# SCH_8_MCP23017_IC_SS_2021-10-14.net
KiCad netlist of a schematic drawn in EasyEDA
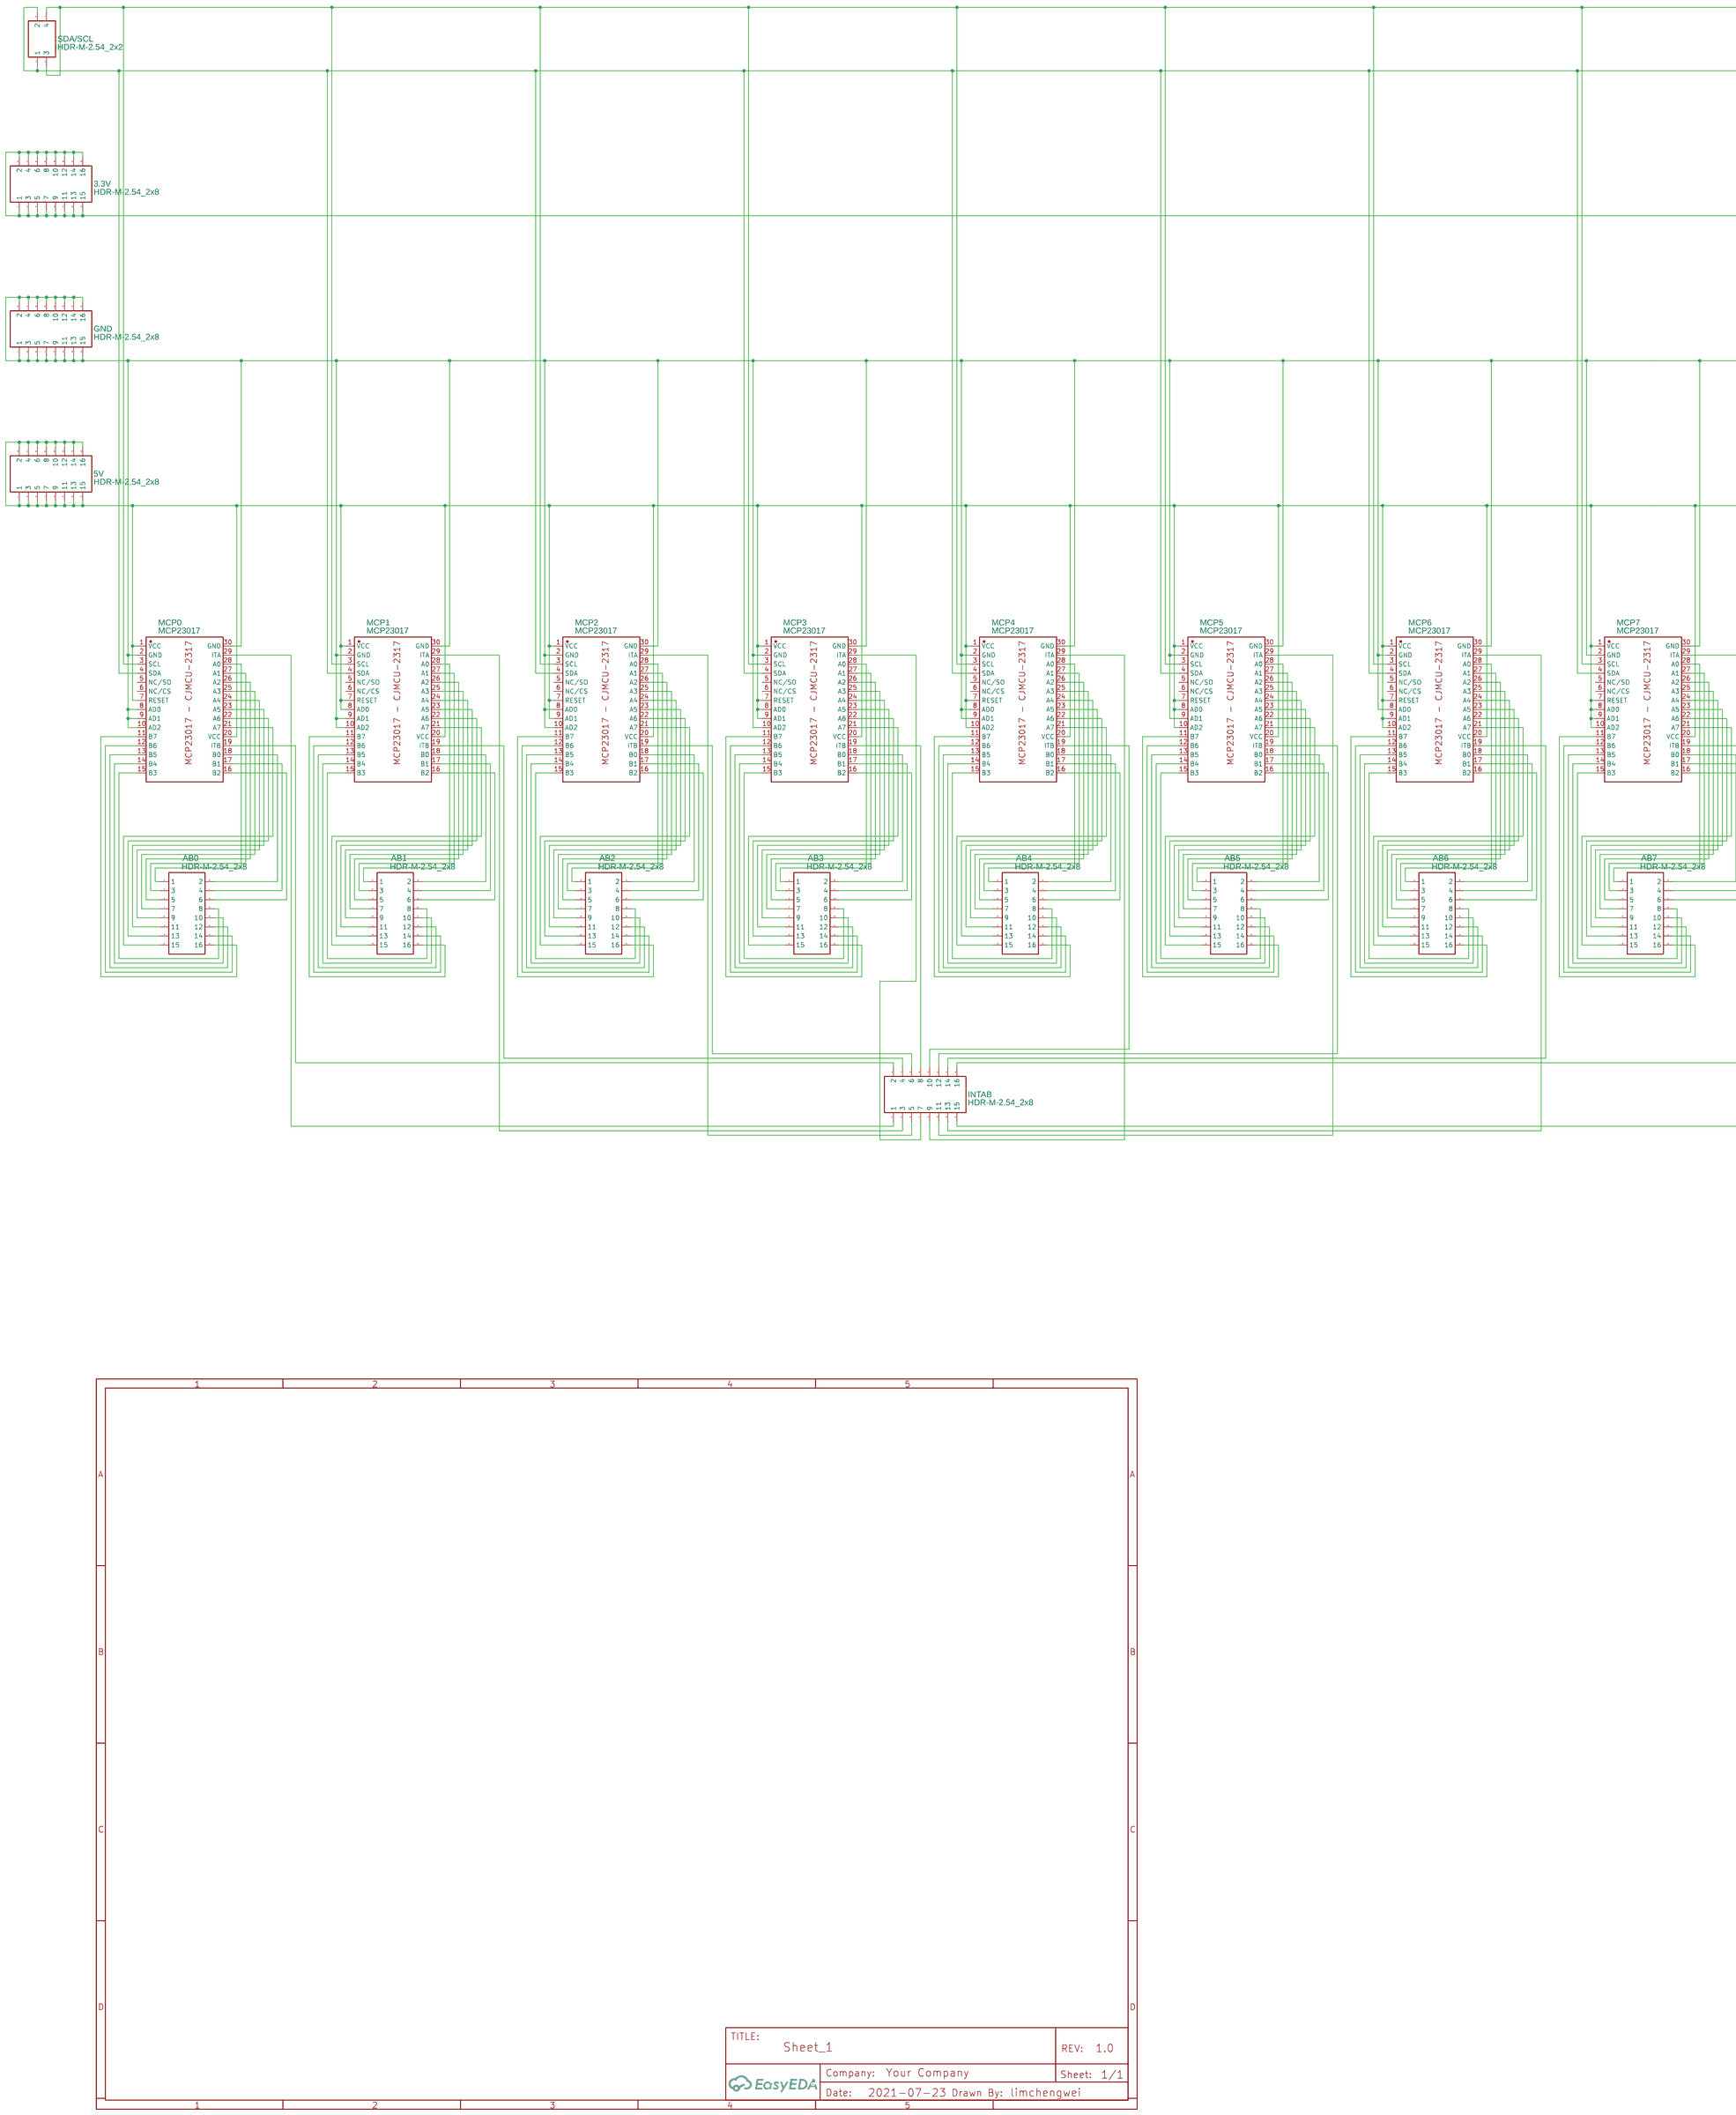
[diagram p0: schematic sheet]

(export (version "E")
  (design (tool "Eeschema 10.0.6"))
  (components
    (comp (ref "3.3V")
      (value "HDR-M-2.54_2x8")
      (fields (field (name "BOM_Supplier Part") "C68234"))
      (libsource (lib "") (part "HDR-M-2.54_2x8_3"))
    )
    (comp (ref "5V")
      (value "HDR-M-2.54_2x8")
      (fields (field (name "BOM_Supplier Part") "C68234"))
      (libsource (lib "") (part "HDR-M-2.54_2x8_1"))
    )
    (comp (ref "AB0")
      (value "HDR-M-2.54_2x8")
      (fields (field (name "BOM_Supplier Part") "C68234"))
      (libsource (lib "") (part "HDR-M-2.54_2x8"))
    )
    (comp (ref "AB1")
      (value "HDR-M-2.54_2x8")
      (fields (field (name "BOM_Supplier Part") "C68234"))
      (libsource (lib "") (part "HDR-M-2.54_2x8"))
    )
    (comp (ref "AB2")
      (value "HDR-M-2.54_2x8")
      (fields (field (name "BOM_Supplier Part") "C68234"))
      (libsource (lib "") (part "HDR-M-2.54_2x8"))
    )
    (comp (ref "AB3")
      (value "HDR-M-2.54_2x8")
      (fields (field (name "BOM_Supplier Part") "C68234"))
      (libsource (lib "") (part "HDR-M-2.54_2x8"))
    )
    (comp (ref "AB4")
      (value "HDR-M-2.54_2x8")
      (fields (field (name "BOM_Supplier Part") "C68234"))
      (libsource (lib "") (part "HDR-M-2.54_2x8"))
    )
    (comp (ref "AB5")
      (value "HDR-M-2.54_2x8")
      (fields (field (name "BOM_Supplier Part") "C68234"))
      (libsource (lib "") (part "HDR-M-2.54_2x8"))
    )
    (comp (ref "AB6")
      (value "HDR-M-2.54_2x8")
      (fields (field (name "BOM_Supplier Part") "C68234"))
      (libsource (lib "") (part "HDR-M-2.54_2x8"))
    )
    (comp (ref "AB7")
      (value "HDR-M-2.54_2x8")
      (fields (field (name "BOM_Supplier Part") "C68234"))
      (libsource (lib "") (part "HDR-M-2.54_2x8"))
    )
    (comp (ref "GND")
      (value "HDR-M-2.54_2x8")
      (fields (field (name "BOM_Supplier Part") "C68234"))
      (libsource (lib "") (part "HDR-M-2.54_2x8_4"))
    )
    (comp (ref "INTAB")
      (value "HDR-M-2.54_2x8")
      (fields (field (name "BOM_Supplier Part") "C68234"))
      (libsource (lib "") (part "HDR-M-2.54_2x8_2"))
    )
    (comp (ref "MCP0") (value "MCP23017") (libsource (lib "") (part "MCP23017")))
    (comp (ref "MCP1") (value "MCP23017") (libsource (lib "") (part "MCP23017")))
    (comp (ref "MCP2") (value "MCP23017") (libsource (lib "") (part "MCP23017")))
    (comp (ref "MCP3") (value "MCP23017") (libsource (lib "") (part "MCP23017")))
    (comp (ref "MCP4") (value "MCP23017") (libsource (lib "") (part "MCP23017")))
    (comp (ref "MCP5") (value "MCP23017") (libsource (lib "") (part "MCP23017")))
    (comp (ref "MCP6") (value "MCP23017") (libsource (lib "") (part "MCP23017")))
    (comp (ref "MCP7") (value "MCP23017") (libsource (lib "") (part "MCP23017")))
    (comp (ref "SDA/SCL")
      (value "HDR-M-2.54_2x2")
      (fields (field (name "BOM_Supplier Part") "C66690"))
      (libsource (lib "") (part "HDR-M-2.54_2x2"))
    )
  )
  (nets
    (net (code "1") (name "Net-(3.3V-Pad1)") (class "Default")
      (node (ref "3.3V") (pin "1") (pinfunction "1_1") (pintype "input"))
      (node (ref "3.3V") (pin "10") (pinfunction "10_10") (pintype "input"))
      (node (ref "3.3V") (pin "11") (pinfunction "11_11") (pintype "input"))
      (node (ref "3.3V") (pin "12") (pinfunction "12_12") (pintype "input"))
      (node (ref "3.3V") (pin "13") (pinfunction "13_13") (pintype "input"))
      (node (ref "3.3V") (pin "14") (pinfunction "14_14") (pintype "input"))
      (node (ref "3.3V") (pin "15") (pinfunction "15_15") (pintype "input"))
      (node (ref "3.3V") (pin "16") (pinfunction "16_16") (pintype "input"))
      (node (ref "3.3V") (pin "2") (pinfunction "2_2") (pintype "input"))
      (node (ref "3.3V") (pin "3") (pinfunction "3_3") (pintype "input"))
      (node (ref "3.3V") (pin "4") (pinfunction "4_4") (pintype "input"))
      (node (ref "3.3V") (pin "5") (pinfunction "5_5") (pintype "input"))
      (node (ref "3.3V") (pin "6") (pinfunction "6_6") (pintype "input"))
      (node (ref "3.3V") (pin "7") (pinfunction "7_7") (pintype "input"))
      (node (ref "3.3V") (pin "8") (pinfunction "8_8") (pintype "input"))
      (node (ref "3.3V") (pin "9") (pinfunction "9_9") (pintype "input"))
    )
    (net (code "2") (name "Net-(MCP0-A0)") (class "Default")
      (node (ref "AB0") (pin "1") (pinfunction "1_1") (pintype "input"))
      (node (ref "MCP0") (pin "28") (pinfunction "A0_28") (pintype "unspecified"))
    )
    (net (code "3") (name "Net-(MCP0-A1)") (class "Default")
      (node (ref "AB0") (pin "3") (pinfunction "3_3") (pintype "input"))
      (node (ref "MCP0") (pin "27") (pinfunction "A1_27") (pintype "unspecified"))
    )
    (net (code "4") (name "Net-(MCP0-A2)") (class "Default")
      (node (ref "AB0") (pin "5") (pinfunction "5_5") (pintype "input"))
      (node (ref "MCP0") (pin "26") (pinfunction "A2_26") (pintype "unspecified"))
    )
    (net (code "5") (name "Net-(MCP0-A3)") (class "Default")
      (node (ref "AB0") (pin "7") (pinfunction "7_7") (pintype "input"))
      (node (ref "MCP0") (pin "25") (pinfunction "A3_25") (pintype "unspecified"))
    )
    (net (code "6") (name "Net-(MCP0-A4)") (class "Default")
      (node (ref "AB0") (pin "9") (pinfunction "9_9") (pintype "input"))
      (node (ref "MCP0") (pin "24") (pinfunction "A4_24") (pintype "unspecified"))
    )
    (net (code "7") (name "Net-(MCP0-A5)") (class "Default")
      (node (ref "AB0") (pin "11") (pinfunction "11_11") (pintype "input"))
      (node (ref "MCP0") (pin "23") (pinfunction "A5_23") (pintype "unspecified"))
    )
    (net (code "8") (name "Net-(MCP0-A6)") (class "Default")
      (node (ref "AB0") (pin "13") (pinfunction "13_13") (pintype "input"))
      (node (ref "MCP0") (pin "22") (pinfunction "A6_22") (pintype "unspecified"))
    )
    (net (code "9") (name "Net-(MCP0-A7)") (class "Default")
      (node (ref "AB0") (pin "15") (pinfunction "15_15") (pintype "input"))
      (node (ref "MCP0") (pin "21") (pinfunction "A7_21") (pintype "unspecified"))
    )
    (net (code "10") (name "Net-(MCP0-AD0)") (class "Default")
      (node (ref "GND") (pin "1") (pinfunction "1_1") (pintype "input"))
      (node (ref "GND") (pin "10") (pinfunction "10_10") (pintype "input"))
      (node (ref "GND") (pin "11") (pinfunction "11_11") (pintype "input"))
      (node (ref "GND") (pin "12") (pinfunction "12_12") (pintype "input"))
      (node (ref "GND") (pin "13") (pinfunction "13_13") (pintype "input"))
      (node (ref "GND") (pin "14") (pinfunction "14_14") (pintype "input"))
      (node (ref "GND") (pin "15") (pinfunction "15_15") (pintype "input"))
      (node (ref "GND") (pin "16") (pinfunction "16_16") (pintype "input"))
      (node (ref "GND") (pin "2") (pinfunction "2_2") (pintype "input"))
      (node (ref "GND") (pin "3") (pinfunction "3_3") (pintype "input"))
      (node (ref "GND") (pin "4") (pinfunction "4_4") (pintype "input"))
      (node (ref "GND") (pin "5") (pinfunction "5_5") (pintype "input"))
      (node (ref "GND") (pin "6") (pinfunction "6_6") (pintype "input"))
      (node (ref "GND") (pin "7") (pinfunction "7_7") (pintype "input"))
      (node (ref "GND") (pin "8") (pinfunction "8_8") (pintype "input"))
      (node (ref "GND") (pin "9") (pinfunction "9_9") (pintype "input"))
      (node (ref "MCP0") (pin "10") (pinfunction "AD2_10") (pintype "unspecified"))
      (node (ref "MCP0") (pin "2") (pinfunction "GND_2") (pintype "passive"))
      (node (ref "MCP0") (pin "30") (pinfunction "GND_30") (pintype "passive"))
      (node (ref "MCP0") (pin "8") (pinfunction "AD0_8") (pintype "unspecified"))
      (node (ref "MCP0") (pin "9") (pinfunction "AD1_9") (pintype "unspecified"))
      (node (ref "MCP1") (pin "10") (pinfunction "AD2_10") (pintype "unspecified"))
      (node (ref "MCP1") (pin "2") (pinfunction "GND_2") (pintype "passive"))
      (node (ref "MCP1") (pin "30") (pinfunction "GND_30") (pintype "passive"))
      (node (ref "MCP1") (pin "9") (pinfunction "AD1_9") (pintype "unspecified"))
      (node (ref "MCP2") (pin "10") (pinfunction "AD2_10") (pintype "unspecified"))
      (node (ref "MCP2") (pin "2") (pinfunction "GND_2") (pintype "passive"))
      (node (ref "MCP2") (pin "30") (pinfunction "GND_30") (pintype "passive"))
      (node (ref "MCP2") (pin "8") (pinfunction "AD0_8") (pintype "unspecified"))
      (node (ref "MCP3") (pin "10") (pinfunction "AD2_10") (pintype "unspecified"))
      (node (ref "MCP3") (pin "2") (pinfunction "GND_2") (pintype "passive"))
      (node (ref "MCP3") (pin "30") (pinfunction "GND_30") (pintype "passive"))
      (node (ref "MCP4") (pin "2") (pinfunction "GND_2") (pintype "passive"))
      (node (ref "MCP4") (pin "30") (pinfunction "GND_30") (pintype "passive"))
      (node (ref "MCP4") (pin "8") (pinfunction "AD0_8") (pintype "unspecified"))
      (node (ref "MCP4") (pin "9") (pinfunction "AD1_9") (pintype "unspecified"))
      (node (ref "MCP5") (pin "2") (pinfunction "GND_2") (pintype "passive"))
      (node (ref "MCP5") (pin "30") (pinfunction "GND_30") (pintype "passive"))
      (node (ref "MCP5") (pin "9") (pinfunction "AD1_9") (pintype "unspecified"))
      (node (ref "MCP6") (pin "2") (pinfunction "GND_2") (pintype "passive"))
      (node (ref "MCP6") (pin "30") (pinfunction "GND_30") (pintype "passive"))
      (node (ref "MCP6") (pin "8") (pinfunction "AD0_8") (pintype "unspecified"))
      (node (ref "MCP7") (pin "2") (pinfunction "GND_2") (pintype "passive"))
      (node (ref "MCP7") (pin "30") (pinfunction "GND_30") (pintype "passive"))
    )
    (net (code "11") (name "Net-(MCP0-B0)") (class "Default")
      (node (ref "AB0") (pin "2") (pinfunction "2_2") (pintype "input"))
      (node (ref "MCP0") (pin "18") (pinfunction "B0_18") (pintype "unspecified"))
    )
    (net (code "12") (name "Net-(MCP0-B1)") (class "Default")
      (node (ref "AB0") (pin "4") (pinfunction "4_4") (pintype "input"))
      (node (ref "MCP0") (pin "17") (pinfunction "B1_17") (pintype "unspecified"))
    )
    (net (code "13") (name "Net-(MCP0-B2)") (class "Default")
      (node (ref "AB0") (pin "6") (pinfunction "6_6") (pintype "input"))
      (node (ref "MCP0") (pin "16") (pinfunction "B2_16") (pintype "unspecified"))
    )
    (net (code "14") (name "Net-(MCP0-B3)") (class "Default")
      (node (ref "AB0") (pin "8") (pinfunction "8_8") (pintype "input"))
      (node (ref "MCP0") (pin "15") (pinfunction "B3_15") (pintype "unspecified"))
    )
    (net (code "15") (name "Net-(MCP0-B4)") (class "Default")
      (node (ref "AB0") (pin "10") (pinfunction "10_10") (pintype "input"))
      (node (ref "MCP0") (pin "14") (pinfunction "B4_14") (pintype "unspecified"))
    )
    (net (code "16") (name "Net-(MCP0-B5)") (class "Default")
      (node (ref "AB0") (pin "12") (pinfunction "12_12") (pintype "input"))
      (node (ref "MCP0") (pin "13") (pinfunction "B5_13") (pintype "unspecified"))
    )
    (net (code "17") (name "Net-(MCP0-B6)") (class "Default")
      (node (ref "AB0") (pin "14") (pinfunction "14_14") (pintype "input"))
      (node (ref "MCP0") (pin "12") (pinfunction "B6_12") (pintype "unspecified"))
    )
    (net (code "18") (name "Net-(MCP0-B7)") (class "Default")
      (node (ref "AB0") (pin "16") (pinfunction "16_16") (pintype "input"))
      (node (ref "MCP0") (pin "11") (pinfunction "B7_11") (pintype "unspecified"))
    )
    (net (code "19") (name "Net-(MCP0-ITA)") (class "Default")
      (node (ref "INTAB") (pin "1") (pinfunction "1_1") (pintype "input"))
      (node (ref "MCP0") (pin "29") (pinfunction "ITA_29") (pintype "unspecified"))
    )
    (net (code "20") (name "Net-(MCP0-ITB)") (class "Default")
      (node (ref "INTAB") (pin "2") (pinfunction "2_2") (pintype "input"))
      (node (ref "MCP0") (pin "19") (pinfunction "ITB_19") (pintype "unspecified"))
    )
    (net (code "21") (name "Net-(MCP0-RESET)") (class "Default")
      (node (ref "5V") (pin "1") (pinfunction "1_1") (pintype "input"))
      (node (ref "5V") (pin "10") (pinfunction "10_10") (pintype "input"))
      (node (ref "5V") (pin "11") (pinfunction "11_11") (pintype "input"))
      (node (ref "5V") (pin "12") (pinfunction "12_12") (pintype "input"))
      (node (ref "5V") (pin "13") (pinfunction "13_13") (pintype "input"))
      (node (ref "5V") (pin "14") (pinfunction "14_14") (pintype "input"))
      (node (ref "5V") (pin "15") (pinfunction "15_15") (pintype "input"))
      (node (ref "5V") (pin "16") (pinfunction "16_16") (pintype "input"))
      (node (ref "5V") (pin "2") (pinfunction "2_2") (pintype "input"))
      (node (ref "5V") (pin "3") (pinfunction "3_3") (pintype "input"))
      (node (ref "5V") (pin "4") (pinfunction "4_4") (pintype "input"))
      (node (ref "5V") (pin "5") (pinfunction "5_5") (pintype "input"))
      (node (ref "5V") (pin "6") (pinfunction "6_6") (pintype "input"))
      (node (ref "5V") (pin "7") (pinfunction "7_7") (pintype "input"))
      (node (ref "5V") (pin "8") (pinfunction "8_8") (pintype "input"))
      (node (ref "5V") (pin "9") (pinfunction "9_9") (pintype "input"))
      (node (ref "MCP0") (pin "1") (pinfunction "VCC_1") (pintype "passive"))
      (node (ref "MCP0") (pin "20") (pinfunction "VCC_20") (pintype "passive"))
      (node (ref "MCP0") (pin "7") (pinfunction "RESET_7") (pintype "input"))
      (node (ref "MCP1") (pin "1") (pinfunction "VCC_1") (pintype "passive"))
      (node (ref "MCP1") (pin "20") (pinfunction "VCC_20") (pintype "passive"))
      (node (ref "MCP1") (pin "7") (pinfunction "RESET_7") (pintype "input"))
      (node (ref "MCP1") (pin "8") (pinfunction "AD0_8") (pintype "unspecified"))
      (node (ref "MCP2") (pin "1") (pinfunction "VCC_1") (pintype "passive"))
      (node (ref "MCP2") (pin "20") (pinfunction "VCC_20") (pintype "passive"))
      (node (ref "MCP2") (pin "7") (pinfunction "RESET_7") (pintype "input"))
      (node (ref "MCP2") (pin "9") (pinfunction "AD1_9") (pintype "unspecified"))
      (node (ref "MCP3") (pin "1") (pinfunction "VCC_1") (pintype "passive"))
      (node (ref "MCP3") (pin "20") (pinfunction "VCC_20") (pintype "passive"))
      (node (ref "MCP3") (pin "7") (pinfunction "RESET_7") (pintype "input"))
      (node (ref "MCP3") (pin "8") (pinfunction "AD0_8") (pintype "unspecified"))
      (node (ref "MCP3") (pin "9") (pinfunction "AD1_9") (pintype "unspecified"))
      (node (ref "MCP4") (pin "1") (pinfunction "VCC_1") (pintype "passive"))
      (node (ref "MCP4") (pin "10") (pinfunction "AD2_10") (pintype "unspecified"))
      (node (ref "MCP4") (pin "20") (pinfunction "VCC_20") (pintype "passive"))
      (node (ref "MCP4") (pin "7") (pinfunction "RESET_7") (pintype "input"))
      (node (ref "MCP5") (pin "1") (pinfunction "VCC_1") (pintype "passive"))
      (node (ref "MCP5") (pin "10") (pinfunction "AD2_10") (pintype "unspecified"))
      (node (ref "MCP5") (pin "20") (pinfunction "VCC_20") (pintype "passive"))
      (node (ref "MCP5") (pin "7") (pinfunction "RESET_7") (pintype "input"))
      (node (ref "MCP5") (pin "8") (pinfunction "AD0_8") (pintype "unspecified"))
      (node (ref "MCP6") (pin "1") (pinfunction "VCC_1") (pintype "passive"))
      (node (ref "MCP6") (pin "10") (pinfunction "AD2_10") (pintype "unspecified"))
      (node (ref "MCP6") (pin "20") (pinfunction "VCC_20") (pintype "passive"))
      (node (ref "MCP6") (pin "7") (pinfunction "RESET_7") (pintype "input"))
      (node (ref "MCP6") (pin "9") (pinfunction "AD1_9") (pintype "unspecified"))
      (node (ref "MCP7") (pin "1") (pinfunction "VCC_1") (pintype "passive"))
      (node (ref "MCP7") (pin "10") (pinfunction "AD2_10") (pintype "unspecified"))
      (node (ref "MCP7") (pin "20") (pinfunction "VCC_20") (pintype "passive"))
      (node (ref "MCP7") (pin "7") (pinfunction "RESET_7") (pintype "input"))
      (node (ref "MCP7") (pin "8") (pinfunction "AD0_8") (pintype "unspecified"))
      (node (ref "MCP7") (pin "9") (pinfunction "AD1_9") (pintype "unspecified"))
    )
    (net (code "22") (name "Net-(MCP0-SCL)") (class "Default")
      (node (ref "MCP0") (pin "3") (pinfunction "SCL_3") (pintype "bidirectional"))
      (node (ref "MCP1") (pin "3") (pinfunction "SCL_3") (pintype "bidirectional"))
      (node (ref "MCP2") (pin "3") (pinfunction "SCL_3") (pintype "bidirectional"))
      (node (ref "MCP3") (pin "3") (pinfunction "SCL_3") (pintype "bidirectional"))
      (node (ref "MCP4") (pin "3") (pinfunction "SCL_3") (pintype "bidirectional"))
      (node (ref "MCP5") (pin "3") (pinfunction "SCL_3") (pintype "bidirectional"))
      (node (ref "MCP6") (pin "3") (pinfunction "SCL_3") (pintype "bidirectional"))
      (node (ref "MCP7") (pin "3") (pinfunction "SCL_3") (pintype "bidirectional"))
      (node (ref "SDA/SCL") (pin "3") (pinfunction "3_3") (pintype "input"))
      (node (ref "SDA/SCL") (pin "4") (pinfunction "4_4") (pintype "input"))
    )
    (net (code "23") (name "Net-(MCP0-SDA)") (class "Default")
      (node (ref "MCP0") (pin "4") (pinfunction "SDA_4") (pintype "bidirectional"))
      (node (ref "MCP1") (pin "4") (pinfunction "SDA_4") (pintype "bidirectional"))
      (node (ref "MCP2") (pin "4") (pinfunction "SDA_4") (pintype "bidirectional"))
      (node (ref "MCP3") (pin "4") (pinfunction "SDA_4") (pintype "bidirectional"))
      (node (ref "MCP4") (pin "4") (pinfunction "SDA_4") (pintype "bidirectional"))
      (node (ref "MCP5") (pin "4") (pinfunction "SDA_4") (pintype "bidirectional"))
      (node (ref "MCP6") (pin "4") (pinfunction "SDA_4") (pintype "bidirectional"))
      (node (ref "MCP7") (pin "4") (pinfunction "SDA_4") (pintype "bidirectional"))
      (node (ref "SDA/SCL") (pin "1") (pinfunction "1_1") (pintype "input"))
      (node (ref "SDA/SCL") (pin "2") (pinfunction "2_2") (pintype "input"))
    )
    (net (code "24") (name "Net-(MCP1-A0)") (class "Default")
      (node (ref "AB1") (pin "1") (pinfunction "1_1") (pintype "input"))
      (node (ref "MCP1") (pin "28") (pinfunction "A0_28") (pintype "unspecified"))
    )
    (net (code "25") (name "Net-(MCP1-A1)") (class "Default")
      (node (ref "AB1") (pin "3") (pinfunction "3_3") (pintype "input"))
      (node (ref "MCP1") (pin "27") (pinfunction "A1_27") (pintype "unspecified"))
    )
    (net (code "26") (name "Net-(MCP1-A2)") (class "Default")
      (node (ref "AB1") (pin "5") (pinfunction "5_5") (pintype "input"))
      (node (ref "MCP1") (pin "26") (pinfunction "A2_26") (pintype "unspecified"))
    )
    (net (code "27") (name "Net-(MCP1-A3)") (class "Default")
      (node (ref "AB1") (pin "7") (pinfunction "7_7") (pintype "input"))
      (node (ref "MCP1") (pin "25") (pinfunction "A3_25") (pintype "unspecified"))
    )
    (net (code "28") (name "Net-(MCP1-A4)") (class "Default")
      (node (ref "AB1") (pin "9") (pinfunction "9_9") (pintype "input"))
      (node (ref "MCP1") (pin "24") (pinfunction "A4_24") (pintype "unspecified"))
    )
    (net (code "29") (name "Net-(MCP1-A5)") (class "Default")
      (node (ref "AB1") (pin "11") (pinfunction "11_11") (pintype "input"))
      (node (ref "MCP1") (pin "23") (pinfunction "A5_23") (pintype "unspecified"))
    )
    (net (code "30") (name "Net-(MCP1-A6)") (class "Default")
      (node (ref "AB1") (pin "13") (pinfunction "13_13") (pintype "input"))
      (node (ref "MCP1") (pin "22") (pinfunction "A6_22") (pintype "unspecified"))
    )
    (net (code "31") (name "Net-(MCP1-A7)") (class "Default")
      (node (ref "AB1") (pin "15") (pinfunction "15_15") (pintype "input"))
      (node (ref "MCP1") (pin "21") (pinfunction "A7_21") (pintype "unspecified"))
    )
    (net (code "32") (name "Net-(MCP1-B0)") (class "Default")
      (node (ref "AB1") (pin "2") (pinfunction "2_2") (pintype "input"))
      (node (ref "MCP1") (pin "18") (pinfunction "B0_18") (pintype "unspecified"))
    )
    (net (code "33") (name "Net-(MCP1-B1)") (class "Default")
      (node (ref "AB1") (pin "4") (pinfunction "4_4") (pintype "input"))
      (node (ref "MCP1") (pin "17") (pinfunction "B1_17") (pintype "unspecified"))
    )
    (net (code "34") (name "Net-(MCP1-B2)") (class "Default")
      (node (ref "AB1") (pin "6") (pinfunction "6_6") (pintype "input"))
      (node (ref "MCP1") (pin "16") (pinfunction "B2_16") (pintype "unspecified"))
    )
    (net (code "35") (name "Net-(MCP1-B3)") (class "Default")
      (node (ref "AB1") (pin "8") (pinfunction "8_8") (pintype "input"))
      (node (ref "MCP1") (pin "15") (pinfunction "B3_15") (pintype "unspecified"))
    )
    (net (code "36") (name "Net-(MCP1-B4)") (class "Default")
      (node (ref "AB1") (pin "10") (pinfunction "10_10") (pintype "input"))
      (node (ref "MCP1") (pin "14") (pinfunction "B4_14") (pintype "unspecified"))
    )
    (net (code "37") (name "Net-(MCP1-B5)") (class "Default")
      (node (ref "AB1") (pin "12") (pinfunction "12_12") (pintype "input"))
      (node (ref "MCP1") (pin "13") (pinfunction "B5_13") (pintype "unspecified"))
    )
    (net (code "38") (name "Net-(MCP1-B6)") (class "Default")
      (node (ref "AB1") (pin "14") (pinfunction "14_14") (pintype "input"))
      (node (ref "MCP1") (pin "12") (pinfunction "B6_12") (pintype "unspecified"))
    )
    (net (code "39") (name "Net-(MCP1-B7)") (class "Default")
      (node (ref "AB1") (pin "16") (pinfunction "16_16") (pintype "input"))
      (node (ref "MCP1") (pin "11") (pinfunction "B7_11") (pintype "unspecified"))
    )
    (net (code "40") (name "Net-(MCP1-ITA)") (class "Default")
      (node (ref "INTAB") (pin "3") (pinfunction "3_3") (pintype "input"))
      (node (ref "MCP1") (pin "29") (pinfunction "ITA_29") (pintype "unspecified"))
    )
    (net (code "41") (name "Net-(MCP1-ITB)") (class "Default")
      (node (ref "INTAB") (pin "4") (pinfunction "4_4") (pintype "input"))
      (node (ref "MCP1") (pin "19") (pinfunction "ITB_19") (pintype "unspecified"))
    )
    (net (code "42") (name "Net-(MCP2-A0)") (class "Default")
      (node (ref "AB2") (pin "1") (pinfunction "1_1") (pintype "input"))
      (node (ref "MCP2") (pin "28") (pinfunction "A0_28") (pintype "unspecified"))
    )
    (net (code "43") (name "Net-(MCP2-A1)") (class "Default")
      (node (ref "AB2") (pin "3") (pinfunction "3_3") (pintype "input"))
      (node (ref "MCP2") (pin "27") (pinfunction "A1_27") (pintype "unspecified"))
    )
    (net (code "44") (name "Net-(MCP2-A2)") (class "Default")
      (node (ref "AB2") (pin "5") (pinfunction "5_5") (pintype "input"))
      (node (ref "MCP2") (pin "26") (pinfunction "A2_26") (pintype "unspecified"))
    )
    (net (code "45") (name "Net-(MCP2-A3)") (class "Default")
      (node (ref "AB2") (pin "7") (pinfunction "7_7") (pintype "input"))
      (node (ref "MCP2") (pin "25") (pinfunction "A3_25") (pintype "unspecified"))
    )
    (net (code "46") (name "Net-(MCP2-A4)") (class "Default")
      (node (ref "AB2") (pin "9") (pinfunction "9_9") (pintype "input"))
      (node (ref "MCP2") (pin "24") (pinfunction "A4_24") (pintype "unspecified"))
    )
    (net (code "47") (name "Net-(MCP2-A5)") (class "Default")
      (node (ref "AB2") (pin "11") (pinfunction "11_11") (pintype "input"))
      (node (ref "MCP2") (pin "23") (pinfunction "A5_23") (pintype "unspecified"))
    )
    (net (code "48") (name "Net-(MCP2-A6)") (class "Default")
      (node (ref "AB2") (pin "13") (pinfunction "13_13") (pintype "input"))
      (node (ref "MCP2") (pin "22") (pinfunction "A6_22") (pintype "unspecified"))
    )
    (net (code "49") (name "Net-(MCP2-A7)") (class "Default")
      (node (ref "AB2") (pin "15") (pinfunction "15_15") (pintype "input"))
      (node (ref "MCP2") (pin "21") (pinfunction "A7_21") (pintype "unspecified"))
    )
    (net (code "50") (name "Net-(MCP2-B0)") (class "Default")
      (node (ref "AB2") (pin "2") (pinfunction "2_2") (pintype "input"))
      (node (ref "MCP2") (pin "18") (pinfunction "B0_18") (pintype "unspecified"))
    )
    (net (code "51") (name "Net-(MCP2-B1)") (class "Default")
      (node (ref "AB2") (pin "4") (pinfunction "4_4") (pintype "input"))
      (node (ref "MCP2") (pin "17") (pinfunction "B1_17") (pintype "unspecified"))
    )
    (net (code "52") (name "Net-(MCP2-B2)") (class "Default")
      (node (ref "AB2") (pin "6") (pinfunction "6_6") (pintype "input"))
      (node (ref "MCP2") (pin "16") (pinfunction "B2_16") (pintype "unspecified"))
    )
    (net (code "53") (name "Net-(MCP2-B3)") (class "Default")
      (node (ref "AB2") (pin "8") (pinfunction "8_8") (pintype "input"))
      (node (ref "MCP2") (pin "15") (pinfunction "B3_15") (pintype "unspecified"))
    )
    (net (code "54") (name "Net-(MCP2-B4)") (class "Default")
      (node (ref "AB2") (pin "10") (pinfunction "10_10") (pintype "input"))
      (node (ref "MCP2") (pin "14") (pinfunction "B4_14") (pintype "unspecified"))
    )
    (net (code "55") (name "Net-(MCP2-B5)") (class "Default")
      (node (ref "AB2") (pin "12") (pinfunction "12_12") (pintype "input"))
      (node (ref "MCP2") (pin "13") (pinfunction "B5_13") (pintype "unspecified"))
    )
    (net (code "56") (name "Net-(MCP2-B6)") (class "Default")
      (node (ref "AB2") (pin "14") (pinfunction "14_14") (pintype "input"))
      (node (ref "MCP2") (pin "12") (pinfunction "B6_12") (pintype "unspecified"))
    )
    (net (code "57") (name "Net-(MCP2-B7)") (class "Default")
      (node (ref "AB2") (pin "16") (pinfunction "16_16") (pintype "input"))
      (node (ref "MCP2") (pin "11") (pinfunction "B7_11") (pintype "unspecified"))
    )
    (net (code "58") (name "Net-(MCP2-ITA)") (class "Default")
      (node (ref "INTAB") (pin "5") (pinfunction "5_5") (pintype "input"))
      (node (ref "MCP2") (pin "29") (pinfunction "ITA_29") (pintype "unspecified"))
    )
    (net (code "59") (name "Net-(MCP2-ITB)") (class "Default")
      (node (ref "INTAB") (pin "6") (pinfunction "6_6") (pintype "input"))
      (node (ref "MCP2") (pin "19") (pinfunction "ITB_19") (pintype "unspecified"))
    )
    (net (code "60") (name "Net-(MCP3-A0)") (class "Default")
      (node (ref "AB3") (pin "1") (pinfunction "1_1") (pintype "input"))
      (node (ref "MCP3") (pin "28") (pinfunction "A0_28") (pintype "unspecified"))
    )
    (net (code "61") (name "Net-(MCP3-A1)") (class "Default")
      (node (ref "AB3") (pin "3") (pinfunction "3_3") (pintype "input"))
      (node (ref "MCP3") (pin "27") (pinfunction "A1_27") (pintype "unspecified"))
    )
    (net (code "62") (name "Net-(MCP3-A2)") (class "Default")
      (node (ref "AB3") (pin "5") (pinfunction "5_5") (pintype "input"))
      (node (ref "MCP3") (pin "26") (pinfunction "A2_26") (pintype "unspecified"))
    )
    (net (code "63") (name "Net-(MCP3-A3)") (class "Default")
      (node (ref "AB3") (pin "7") (pinfunction "7_7") (pintype "input"))
      (node (ref "MCP3") (pin "25") (pinfunction "A3_25") (pintype "unspecified"))
    )
    (net (code "64") (name "Net-(MCP3-A4)") (class "Default")
      (node (ref "AB3") (pin "9") (pinfunction "9_9") (pintype "input"))
      (node (ref "MCP3") (pin "24") (pinfunction "A4_24") (pintype "unspecified"))
    )
    (net (code "65") (name "Net-(MCP3-A5)") (class "Default")
      (node (ref "AB3") (pin "11") (pinfunction "11_11") (pintype "input"))
      (node (ref "MCP3") (pin "23") (pinfunction "A5_23") (pintype "unspecified"))
    )
    (net (code "66") (name "Net-(MCP3-A6)") (class "Default")
      (node (ref "AB3") (pin "13") (pinfunction "13_13") (pintype "input"))
      (node (ref "MCP3") (pin "22") (pinfunction "A6_22") (pintype "unspecified"))
    )
    (net (code "67") (name "Net-(MCP3-A7)") (class "Default")
      (node (ref "AB3") (pin "15") (pinfunction "15_15") (pintype "input"))
      (node (ref "MCP3") (pin "21") (pinfunction "A7_21") (pintype "unspecified"))
    )
    (net (code "68") (name "Net-(MCP3-B0)") (class "Default")
      (node (ref "AB3") (pin "2") (pinfunction "2_2") (pintype "input"))
      (node (ref "MCP3") (pin "18") (pinfunction "B0_18") (pintype "unspecified"))
    )
    (net (code "69") (name "Net-(MCP3-B1)") (class "Default")
      (node (ref "AB3") (pin "4") (pinfunction "4_4") (pintype "input"))
      (node (ref "MCP3") (pin "17") (pinfunction "B1_17") (pintype "unspecified"))
    )
    (net (code "70") (name "Net-(MCP3-B2)") (class "Default")
      (node (ref "AB3") (pin "6") (pinfunction "6_6") (pintype "input"))
      (node (ref "MCP3") (pin "16") (pinfunction "B2_16") (pintype "unspecified"))
    )
    (net (code "71") (name "Net-(MCP3-B3)") (class "Default")
      (node (ref "AB3") (pin "8") (pinfunction "8_8") (pintype "input"))
      (node (ref "MCP3") (pin "15") (pinfunction "B3_15") (pintype "unspecified"))
    )
    (net (code "72") (name "Net-(MCP3-B4)") (class "Default")
      (node (ref "AB3") (pin "10") (pinfunction "10_10") (pintype "input"))
      (node (ref "MCP3") (pin "14") (pinfunction "B4_14") (pintype "unspecified"))
    )
    (net (code "73") (name "Net-(MCP3-B5)") (class "Default")
      (node (ref "AB3") (pin "12") (pinfunction "12_12") (pintype "input"))
      (node (ref "MCP3") (pin "13") (pinfunction "B5_13") (pintype "unspecified"))
    )
    (net (code "74") (name "Net-(MCP3-B6)") (class "Default")
      (node (ref "AB3") (pin "14") (pinfunction "14_14") (pintype "input"))
      (node (ref "MCP3") (pin "12") (pinfunction "B6_12") (pintype "unspecified"))
    )
    (net (code "75") (name "Net-(MCP3-B7)") (class "Default")
      (node (ref "AB3") (pin "16") (pinfunction "16_16") (pintype "input"))
      (node (ref "MCP3") (pin "11") (pinfunction "B7_11") (pintype "unspecified"))
    )
    (net (code "76") (name "Net-(MCP3-ITA)") (class "Default")
      (node (ref "INTAB") (pin "7") (pinfunction "7_7") (pintype "input"))
      (node (ref "MCP3") (pin "29") (pinfunction "ITA_29") (pintype "unspecified"))
    )
    (net (code "77") (name "Net-(MCP3-ITB)") (class "Default")
      (node (ref "INTAB") (pin "8") (pinfunction "8_8") (pintype "input"))
      (node (ref "MCP3") (pin "19") (pinfunction "ITB_19") (pintype "unspecified"))
    )
    (net (code "78") (name "Net-(MCP4-A0)") (class "Default")
      (node (ref "AB4") (pin "1") (pinfunction "1_1") (pintype "input"))
      (node (ref "MCP4") (pin "28") (pinfunction "A0_28") (pintype "unspecified"))
    )
    (net (code "79") (name "Net-(MCP4-A1)") (class "Default")
      (node (ref "AB4") (pin "3") (pinfunction "3_3") (pintype "input"))
      (node (ref "MCP4") (pin "27") (pinfunction "A1_27") (pintype "unspecified"))
    )
    (net (code "80") (name "Net-(MCP4-A2)") (class "Default")
      (node (ref "AB4") (pin "5") (pinfunction "5_5") (pintype "input"))
      (node (ref "MCP4") (pin "26") (pinfunction "A2_26") (pintype "unspecified"))
    )
    (net (code "81") (name "Net-(MCP4-A3)") (class "Default")
      (node (ref "AB4") (pin "7") (pinfunction "7_7") (pintype "input"))
      (node (ref "MCP4") (pin "25") (pinfunction "A3_25") (pintype "unspecified"))
    )
    (net (code "82") (name "Net-(MCP4-A4)") (class "Default")
      (node (ref "AB4") (pin "9") (pinfunction "9_9") (pintype "input"))
      (node (ref "MCP4") (pin "24") (pinfunction "A4_24") (pintype "unspecified"))
    )
    (net (code "83") (name "Net-(MCP4-A5)") (class "Default")
      (node (ref "AB4") (pin "11") (pinfunction "11_11") (pintype "input"))
      (node (ref "MCP4") (pin "23") (pinfunction "A5_23") (pintype "unspecified"))
    )
    (net (code "84") (name "Net-(MCP4-A6)") (class "Default")
      (node (ref "AB4") (pin "13") (pinfunction "13_13") (pintype "input"))
      (node (ref "MCP4") (pin "22") (pinfunction "A6_22") (pintype "unspecified"))
    )
    (net (code "85") (name "Net-(MCP4-A7)") (class "Default")
      (node (ref "AB4") (pin "15") (pinfunction "15_15") (pintype "input"))
      (node (ref "MCP4") (pin "21") (pinfunction "A7_21") (pintype "unspecified"))
    )
    (net (code "86") (name "Net-(MCP4-B0)") (class "Default")
      (node (ref "AB4") (pin "2") (pinfunction "2_2") (pintype "input"))
      (node (ref "MCP4") (pin "18") (pinfunction "B0_18") (pintype "unspecified"))
    )
    (net (code "87") (name "Net-(MCP4-B1)") (class "Default")
      (node (ref "AB4") (pin "4") (pinfunction "4_4") (pintype "input"))
      (node (ref "MCP4") (pin "17") (pinfunction "B1_17") (pintype "unspecified"))
    )
    (net (code "88") (name "Net-(MCP4-B2)") (class "Default")
      (node (ref "AB4") (pin "6") (pinfunction "6_6") (pintype "input"))
      (node (ref "MCP4") (pin "16") (pinfunction "B2_16") (pintype "unspecified"))
    )
    (net (code "89") (name "Net-(MCP4-B3)") (class "Default")
      (node (ref "AB4") (pin "8") (pinfunction "8_8") (pintype "input"))
      (node (ref "MCP4") (pin "15") (pinfunction "B3_15") (pintype "unspecified"))
    )
    (net (code "90") (name "Net-(MCP4-B4)") (class "Default")
      (node (ref "AB4") (pin "10") (pinfunction "10_10") (pintype "input"))
      (node (ref "MCP4") (pin "14") (pinfunction "B4_14") (pintype "unspecified"))
    )
    (net (code "91") (name "Net-(MCP4-B5)") (class "Default")
      (node (ref "AB4") (pin "12") (pinfunction "12_12") (pintype "input"))
      (node (ref "MCP4") (pin "13") (pinfunction "B5_13") (pintype "unspecified"))
    )
    (net (code "92") (name "Net-(MCP4-B6)") (class "Default")
      (node (ref "AB4") (pin "14") (pinfunction "14_14") (pintype "input"))
      (node (ref "MCP4") (pin "12") (pinfunction "B6_12") (pintype "unspecified"))
    )
    (net (code "93") (name "Net-(MCP4-B7)") (class "Default")
      (node (ref "AB4") (pin "16") (pinfunction "16_16") (pintype "input"))
      (node (ref "MCP4") (pin "11") (pinfunction "B7_11") (pintype "unspecified"))
    )
    (net (code "94") (name "Net-(MCP4-ITA)") (class "Default")
      (node (ref "INTAB") (pin "9") (pinfunction "9_9") (pintype "input"))
      (node (ref "MCP4") (pin "29") (pinfunction "ITA_29") (pintype "unspecified"))
    )
    (net (code "95") (name "Net-(MCP4-ITB)") (class "Default")
      (node (ref "INTAB") (pin "10") (pinfunction "10_10") (pintype "input"))
      (node (ref "MCP4") (pin "19") (pinfunction "ITB_19") (pintype "unspecified"))
    )
    (net (code "96") (name "Net-(MCP5-A0)") (class "Default")
      (node (ref "AB5") (pin "1") (pinfunction "1_1") (pintype "input"))
      (node (ref "MCP5") (pin "28") (pinfunction "A0_28") (pintype "unspecified"))
    )
    (net (code "97") (name "Net-(MCP5-A1)") (class "Default")
      (node (ref "AB5") (pin "3") (pinfunction "3_3") (pintype "input"))
      (node (ref "MCP5") (pin "27") (pinfunction "A1_27") (pintype "unspecified"))
    )
    (net (code "98") (name "Net-(MCP5-A2)") (class "Default")
      (node (ref "AB5") (pin "5") (pinfunction "5_5") (pintype "input"))
      (node (ref "MCP5") (pin "26") (pinfunction "A2_26") (pintype "unspecified"))
    )
    (net (code "99") (name "Net-(MCP5-A3)") (class "Default")
      (node (ref "AB5") (pin "7") (pinfunction "7_7") (pintype "input"))
      (node (ref "MCP5") (pin "25") (pinfunction "A3_25") (pintype "unspecified"))
    )
    (net (code "100") (name "Net-(MCP5-A4)") (class "Default")
      (node (ref "AB5") (pin "9") (pinfunction "9_9") (pintype "input"))
      (node (ref "MCP5") (pin "24") (pinfunction "A4_24") (pintype "unspecified"))
    )
    (net (code "101") (name "Net-(MCP5-A5)") (class "Default")
      (node (ref "AB5") (pin "11") (pinfunction "11_11") (pintype "input"))
      (node (ref "MCP5") (pin "23") (pinfunction "A5_23") (pintype "unspecified"))
    )
    (net (code "102") (name "Net-(MCP5-A6)") (class "Default")
      (node (ref "AB5") (pin "13") (pinfunction "13_13") (pintype "input"))
      (node (ref "MCP5") (pin "22") (pinfunction "A6_22") (pintype "unspecified"))
    )
    (net (code "103") (name "Net-(MCP5-A7)") (class "Default")
      (node (ref "AB5") (pin "15") (pinfunction "15_15") (pintype "input"))
      (node (ref "MCP5") (pin "21") (pinfunction "A7_21") (pintype "unspecified"))
    )
    (net (code "104") (name "Net-(MCP5-B0)") (class "Default")
      (node (ref "AB5") (pin "2") (pinfunction "2_2") (pintype "input"))
      (node (ref "MCP5") (pin "18") (pinfunction "B0_18") (pintype "unspecified"))
    )
    (net (code "105") (name "Net-(MCP5-B1)") (class "Default")
      (node (ref "AB5") (pin "4") (pinfunction "4_4") (pintype "input"))
      (node (ref "MCP5") (pin "17") (pinfunction "B1_17") (pintype "unspecified"))
    )
    (net (code "106") (name "Net-(MCP5-B2)") (class "Default")
      (node (ref "AB5") (pin "6") (pinfunction "6_6") (pintype "input"))
      (node (ref "MCP5") (pin "16") (pinfunction "B2_16") (pintype "unspecified"))
    )
    (net (code "107") (name "Net-(MCP5-B3)") (class "Default")
      (node (ref "AB5") (pin "8") (pinfunction "8_8") (pintype "input"))
      (node (ref "MCP5") (pin "15") (pinfunction "B3_15") (pintype "unspecified"))
    )
    (net (code "108") (name "Net-(MCP5-B4)") (class "Default")
      (node (ref "AB5") (pin "10") (pinfunction "10_10") (pintype "input"))
      (node (ref "MCP5") (pin "14") (pinfunction "B4_14") (pintype "unspecified"))
    )
    (net (code "109") (name "Net-(MCP5-B5)") (class "Default")
      (node (ref "AB5") (pin "12") (pinfunction "12_12") (pintype "input"))
      (node (ref "MCP5") (pin "13") (pinfunction "B5_13") (pintype "unspecified"))
    )
    (net (code "110") (name "Net-(MCP5-B6)") (class "Default")
      (node (ref "AB5") (pin "14") (pinfunction "14_14") (pintype "input"))
      (node (ref "MCP5") (pin "12") (pinfunction "B6_12") (pintype "unspecified"))
    )
    (net (code "111") (name "Net-(MCP5-B7)") (class "Default")
      (node (ref "AB5") (pin "16") (pinfunction "16_16") (pintype "input"))
      (node (ref "MCP5") (pin "11") (pinfunction "B7_11") (pintype "unspecified"))
    )
    (net (code "112") (name "Net-(MCP5-ITA)") (class "Default")
      (node (ref "INTAB") (pin "11") (pinfunction "11_11") (pintype "input"))
      (node (ref "MCP5") (pin "29") (pinfunction "ITA_29") (pintype "unspecified"))
    )
    (net (code "113") (name "Net-(MCP5-ITB)") (class "Default")
      (node (ref "INTAB") (pin "12") (pinfunction "12_12") (pintype "input"))
      (node (ref "MCP5") (pin "19") (pinfunction "ITB_19") (pintype "unspecified"))
    )
    (net (code "114") (name "Net-(MCP6-A0)") (class "Default")
      (node (ref "AB6") (pin "1") (pinfunction "1_1") (pintype "input"))
      (node (ref "MCP6") (pin "28") (pinfunction "A0_28") (pintype "unspecified"))
    )
    (net (code "115") (name "Net-(MCP6-A1)") (class "Default")
      (node (ref "AB6") (pin "3") (pinfunction "3_3") (pintype "input"))
      (node (ref "MCP6") (pin "27") (pinfunction "A1_27") (pintype "unspecified"))
    )
    (net (code "116") (name "Net-(MCP6-A2)") (class "Default")
      (node (ref "AB6") (pin "5") (pinfunction "5_5") (pintype "input"))
      (node (ref "MCP6") (pin "26") (pinfunction "A2_26") (pintype "unspecified"))
    )
    (net (code "117") (name "Net-(MCP6-A3)") (class "Default")
      (node (ref "AB6") (pin "7") (pinfunction "7_7") (pintype "input"))
      (node (ref "MCP6") (pin "25") (pinfunction "A3_25") (pintype "unspecified"))
    )
    (net (code "118") (name "Net-(MCP6-A4)") (class "Default")
      (node (ref "AB6") (pin "9") (pinfunction "9_9") (pintype "input"))
      (node (ref "MCP6") (pin "24") (pinfunction "A4_24") (pintype "unspecified"))
    )
    (net (code "119") (name "Net-(MCP6-A5)") (class "Default")
      (node (ref "AB6") (pin "11") (pinfunction "11_11") (pintype "input"))
      (node (ref "MCP6") (pin "23") (pinfunction "A5_23") (pintype "unspecified"))
    )
    (net (code "120") (name "Net-(MCP6-A6)") (class "Default")
      (node (ref "AB6") (pin "13") (pinfunction "13_13") (pintype "input"))
      (node (ref "MCP6") (pin "22") (pinfunction "A6_22") (pintype "unspecified"))
    )
    (net (code "121") (name "Net-(MCP6-A7)") (class "Default")
      (node (ref "AB6") (pin "15") (pinfunction "15_15") (pintype "input"))
      (node (ref "MCP6") (pin "21") (pinfunction "A7_21") (pintype "unspecified"))
    )
    (net (code "122") (name "Net-(MCP6-B0)") (class "Default")
      (node (ref "AB6") (pin "2") (pinfunction "2_2") (pintype "input"))
      (node (ref "MCP6") (pin "18") (pinfunction "B0_18") (pintype "unspecified"))
    )
    (net (code "123") (name "Net-(MCP6-B1)") (class "Default")
      (node (ref "AB6") (pin "4") (pinfunction "4_4") (pintype "input"))
      (node (ref "MCP6") (pin "17") (pinfunction "B1_17") (pintype "unspecified"))
    )
    (net (code "124") (name "Net-(MCP6-B2)") (class "Default")
      (node (ref "AB6") (pin "6") (pinfunction "6_6") (pintype "input"))
      (node (ref "MCP6") (pin "16") (pinfunction "B2_16") (pintype "unspecified"))
    )
    (net (code "125") (name "Net-(MCP6-B3)") (class "Default")
      (node (ref "AB6") (pin "8") (pinfunction "8_8") (pintype "input"))
      (node (ref "MCP6") (pin "15") (pinfunction "B3_15") (pintype "unspecified"))
    )
    (net (code "126") (name "Net-(MCP6-B4)") (class "Default")
      (node (ref "AB6") (pin "10") (pinfunction "10_10") (pintype "input"))
      (node (ref "MCP6") (pin "14") (pinfunction "B4_14") (pintype "unspecified"))
    )
    (net (code "127") (name "Net-(MCP6-B5)") (class "Default")
      (node (ref "AB6") (pin "12") (pinfunction "12_12") (pintype "input"))
      (node (ref "MCP6") (pin "13") (pinfunction "B5_13") (pintype "unspecified"))
    )
    (net (code "128") (name "Net-(MCP6-B6)") (class "Default")
      (node (ref "AB6") (pin "14") (pinfunction "14_14") (pintype "input"))
      (node (ref "MCP6") (pin "12") (pinfunction "B6_12") (pintype "unspecified"))
    )
    (net (code "129") (name "Net-(MCP6-B7)") (class "Default")
      (node (ref "AB6") (pin "16") (pinfunction "16_16") (pintype "input"))
      (node (ref "MCP6") (pin "11") (pinfunction "B7_11") (pintype "unspecified"))
    )
    (net (code "130") (name "Net-(MCP6-ITA)") (class "Default")
      (node (ref "INTAB") (pin "13") (pinfunction "13_13") (pintype "input"))
      (node (ref "MCP6") (pin "29") (pinfunction "ITA_29") (pintype "unspecified"))
    )
    (net (code "131") (name "Net-(MCP6-ITB)") (class "Default")
      (node (ref "INTAB") (pin "14") (pinfunction "14_14") (pintype "input"))
      (node (ref "MCP6") (pin "19") (pinfunction "ITB_19") (pintype "unspecified"))
    )
    (net (code "132") (name "Net-(MCP7-A0)") (class "Default")
      (node (ref "AB7") (pin "1") (pinfunction "1_1") (pintype "input"))
      (node (ref "MCP7") (pin "28") (pinfunction "A0_28") (pintype "unspecified"))
    )
    (net (code "133") (name "Net-(MCP7-A1)") (class "Default")
      (node (ref "AB7") (pin "3") (pinfunction "3_3") (pintype "input"))
      (node (ref "MCP7") (pin "27") (pinfunction "A1_27") (pintype "unspecified"))
    )
    (net (code "134") (name "Net-(MCP7-A2)") (class "Default")
      (node (ref "AB7") (pin "5") (pinfunction "5_5") (pintype "input"))
      (node (ref "MCP7") (pin "26") (pinfunction "A2_26") (pintype "unspecified"))
    )
    (net (code "135") (name "Net-(MCP7-A3)") (class "Default")
      (node (ref "AB7") (pin "7") (pinfunction "7_7") (pintype "input"))
      (node (ref "MCP7") (pin "25") (pinfunction "A3_25") (pintype "unspecified"))
    )
    (net (code "136") (name "Net-(MCP7-A4)") (class "Default")
      (node (ref "AB7") (pin "9") (pinfunction "9_9") (pintype "input"))
      (node (ref "MCP7") (pin "24") (pinfunction "A4_24") (pintype "unspecified"))
    )
    (net (code "137") (name "Net-(MCP7-A5)") (class "Default")
      (node (ref "AB7") (pin "11") (pinfunction "11_11") (pintype "input"))
      (node (ref "MCP7") (pin "23") (pinfunction "A5_23") (pintype "unspecified"))
    )
    (net (code "138") (name "Net-(MCP7-A6)") (class "Default")
      (node (ref "AB7") (pin "13") (pinfunction "13_13") (pintype "input"))
      (node (ref "MCP7") (pin "22") (pinfunction "A6_22") (pintype "unspecified"))
    )
    (net (code "139") (name "Net-(MCP7-A7)") (class "Default")
      (node (ref "AB7") (pin "15") (pinfunction "15_15") (pintype "input"))
      (node (ref "MCP7") (pin "21") (pinfunction "A7_21") (pintype "unspecified"))
    )
    (net (code "140") (name "Net-(MCP7-B0)") (class "Default")
      (node (ref "AB7") (pin "2") (pinfunction "2_2") (pintype "input"))
      (node (ref "MCP7") (pin "18") (pinfunction "B0_18") (pintype "unspecified"))
    )
    (net (code "141") (name "Net-(MCP7-B1)") (class "Default")
      (node (ref "AB7") (pin "4") (pinfunction "4_4") (pintype "input"))
      (node (ref "MCP7") (pin "17") (pinfunction "B1_17") (pintype "unspecified"))
    )
    (net (code "142") (name "Net-(MCP7-B2)") (class "Default")
      (node (ref "AB7") (pin "6") (pinfunction "6_6") (pintype "input"))
      (node (ref "MCP7") (pin "16") (pinfunction "B2_16") (pintype "unspecified"))
    )
    (net (code "143") (name "Net-(MCP7-B3)") (class "Default")
      (node (ref "AB7") (pin "8") (pinfunction "8_8") (pintype "input"))
      (node (ref "MCP7") (pin "15") (pinfunction "B3_15") (pintype "unspecified"))
    )
    (net (code "144") (name "Net-(MCP7-B4)") (class "Default")
      (node (ref "AB7") (pin "10") (pinfunction "10_10") (pintype "input"))
      (node (ref "MCP7") (pin "14") (pinfunction "B4_14") (pintype "unspecified"))
    )
    (net (code "145") (name "Net-(MCP7-B5)") (class "Default")
      (node (ref "AB7") (pin "12") (pinfunction "12_12") (pintype "input"))
      (node (ref "MCP7") (pin "13") (pinfunction "B5_13") (pintype "unspecified"))
    )
    (net (code "146") (name "Net-(MCP7-B6)") (class "Default")
      (node (ref "AB7") (pin "14") (pinfunction "14_14") (pintype "input"))
      (node (ref "MCP7") (pin "12") (pinfunction "B6_12") (pintype "unspecified"))
    )
    (net (code "147") (name "Net-(MCP7-B7)") (class "Default")
      (node (ref "AB7") (pin "16") (pinfunction "16_16") (pintype "input"))
      (node (ref "MCP7") (pin "11") (pinfunction "B7_11") (pintype "unspecified"))
    )
    (net (code "148") (name "Net-(MCP7-ITA)") (class "Default")
      (node (ref "INTAB") (pin "15") (pinfunction "15_15") (pintype "input"))
      (node (ref "MCP7") (pin "29") (pinfunction "ITA_29") (pintype "unspecified"))
    )
    (net (code "149") (name "Net-(MCP7-ITB)") (class "Default")
      (node (ref "INTAB") (pin "16") (pinfunction "16_16") (pintype "input"))
      (node (ref "MCP7") (pin "19") (pinfunction "ITB_19") (pintype "unspecified"))
    )
    (net (code "150") (name "unconnected-(MCP0-NC{slash}CS-Pad6)") (class "Default")
      (node (ref "MCP0") (pin "6") (pinfunction "NC/CS_6") (pintype "unspecified"))
    )
    (net (code "151") (name "unconnected-(MCP0-NC{slash}SO-Pad5)") (class "Default")
      (node (ref "MCP0") (pin "5") (pinfunction "NC/SO_5") (pintype "unspecified"))
    )
    (net (code "152") (name "unconnected-(MCP1-NC{slash}CS-Pad6)") (class "Default")
      (node (ref "MCP1") (pin "6") (pinfunction "NC/CS_6") (pintype "unspecified"))
    )
    (net (code "153") (name "unconnected-(MCP1-NC{slash}SO-Pad5)") (class "Default")
      (node (ref "MCP1") (pin "5") (pinfunction "NC/SO_5") (pintype "unspecified"))
    )
    (net (code "154") (name "unconnected-(MCP2-NC{slash}CS-Pad6)") (class "Default")
      (node (ref "MCP2") (pin "6") (pinfunction "NC/CS_6") (pintype "unspecified"))
    )
    (net (code "155") (name "unconnected-(MCP2-NC{slash}SO-Pad5)") (class "Default")
      (node (ref "MCP2") (pin "5") (pinfunction "NC/SO_5") (pintype "unspecified"))
    )
    (net (code "156") (name "unconnected-(MCP3-NC{slash}CS-Pad6)") (class "Default")
      (node (ref "MCP3") (pin "6") (pinfunction "NC/CS_6") (pintype "unspecified"))
    )
    (net (code "157") (name "unconnected-(MCP3-NC{slash}SO-Pad5)") (class "Default")
      (node (ref "MCP3") (pin "5") (pinfunction "NC/SO_5") (pintype "unspecified"))
    )
    (net (code "158") (name "unconnected-(MCP4-NC{slash}CS-Pad6)") (class "Default")
      (node (ref "MCP4") (pin "6") (pinfunction "NC/CS_6") (pintype "unspecified"))
    )
    (net (code "159") (name "unconnected-(MCP4-NC{slash}SO-Pad5)") (class "Default")
      (node (ref "MCP4") (pin "5") (pinfunction "NC/SO_5") (pintype "unspecified"))
    )
    (net (code "160") (name "unconnected-(MCP5-NC{slash}CS-Pad6)") (class "Default")
      (node (ref "MCP5") (pin "6") (pinfunction "NC/CS_6") (pintype "unspecified"))
    )
    (net (code "161") (name "unconnected-(MCP5-NC{slash}SO-Pad5)") (class "Default")
      (node (ref "MCP5") (pin "5") (pinfunction "NC/SO_5") (pintype "unspecified"))
    )
    (net (code "162") (name "unconnected-(MCP6-NC{slash}CS-Pad6)") (class "Default")
      (node (ref "MCP6") (pin "6") (pinfunction "NC/CS_6") (pintype "unspecified"))
    )
    (net (code "163") (name "unconnected-(MCP6-NC{slash}SO-Pad5)") (class "Default")
      (node (ref "MCP6") (pin "5") (pinfunction "NC/SO_5") (pintype "unspecified"))
    )
    (net (code "164") (name "unconnected-(MCP7-NC{slash}CS-Pad6)") (class "Default")
      (node (ref "MCP7") (pin "6") (pinfunction "NC/CS_6") (pintype "unspecified"))
    )
    (net (code "165") (name "unconnected-(MCP7-NC{slash}SO-Pad5)") (class "Default")
      (node (ref "MCP7") (pin "5") (pinfunction "NC/SO_5") (pintype "unspecified"))
    )
  )
)
